# 468323_001_LED_DRV_ISO_1.net
KiCad netlist of a schematic drawn in Altium Designer
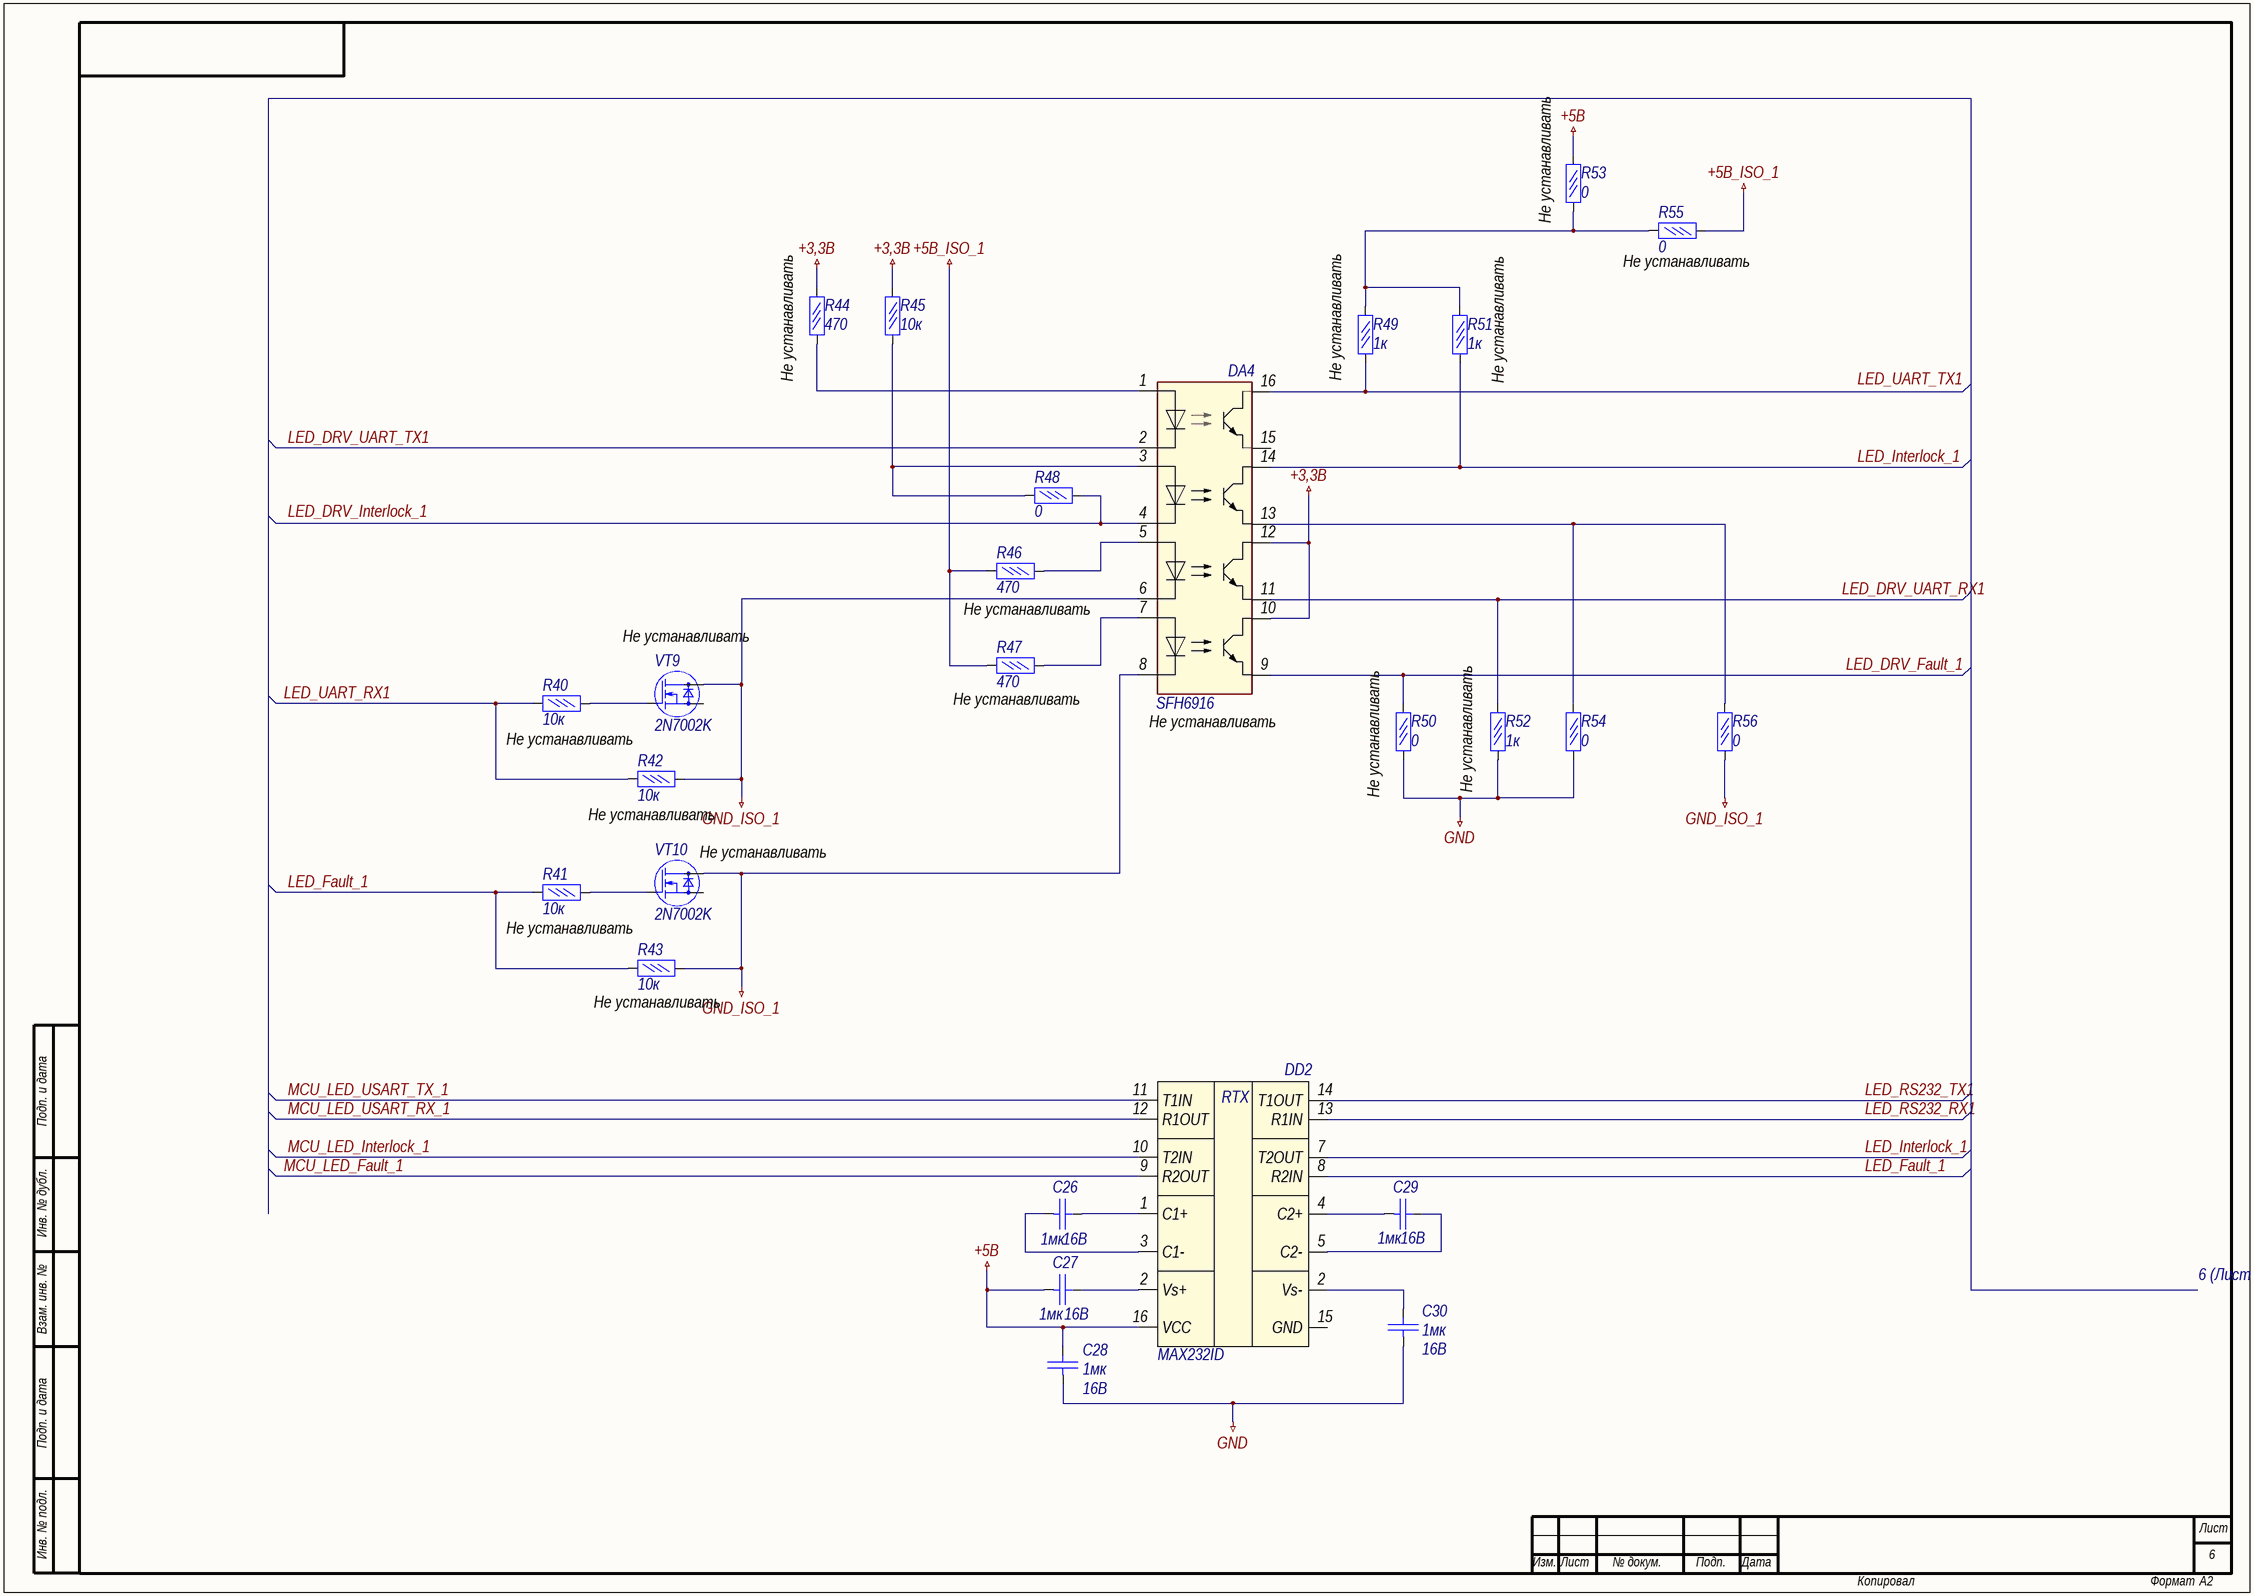
[diagram p0: РЕУН.468323.001_LED_DRV_ISO_1.SchDoc]

(export (version "E")
  (design (tool "Eeschema 10.0.6"))
  (components
    (comp (ref "C26")
      (value "1мк")
      (footprint "C0805_AA")
      (description "Конденсатор кер.")
      (fields (field (name "VOLTAGE") "16В"))
      (libsource (lib "Library_Diana") (part "Конденсатор кер."))
    )
    (comp (ref "C27")
      (value "1мк")
      (footprint "C0805_AA")
      (description "Конденсатор кер.")
      (fields (field (name "VOLTAGE") "16В"))
      (libsource (lib "Library_Diana") (part "Конденсатор кер."))
    )
    (comp (ref "C28")
      (value "1мк")
      (footprint "C0805_AA")
      (description "Конденсатор кер.")
      (fields (field (name "VOLTAGE") "16В"))
      (libsource (lib "Library_Diana") (part "Конденсатор кер."))
    )
    (comp (ref "C29")
      (value "1мк")
      (footprint "C0805_AA")
      (description "Конденсатор кер.")
      (fields (field (name "VOLTAGE") "16В"))
      (libsource (lib "Library_Diana") (part "Конденсатор кер."))
    )
    (comp (ref "C30")
      (value "1мк")
      (footprint "C0805_AA")
      (description "Конденсатор кер.")
      (fields (field (name "VOLTAGE") "16В"))
      (libsource (lib "Library_Diana") (part "Конденсатор кер."))
    )
    (comp (ref "DA4")
      (value "SFH6916")
      (description "Опторазвязка х4")
      (libsource (lib "Library_Diana") (part "OPTO-4"))
    )
    (comp (ref "DD2")
      (value "MAX232ID")
      (description "Dual EIA-232 Drivers/Receivers")
      (libsource (lib "Library_Diana") (part "MAX232ID"))
    )
    (comp (ref "R40")
      (value "10к")
      (footprint "R1206")
      (description "Резистор 0,05Вт")
      (libsource (lib "") (part "Резистор  0,05Вт_1"))
    )
    (comp (ref "R41")
      (value "10к")
      (footprint "R1206")
      (description "Резистор 0,05Вт")
      (libsource (lib "") (part "Резистор  0,05Вт_1"))
    )
    (comp (ref "R42")
      (value "10к")
      (footprint "R1206")
      (description "Резистор 0,05Вт")
      (libsource (lib "") (part "Резистор  0,05Вт_1"))
    )
    (comp (ref "R43")
      (value "10к")
      (footprint "R1206")
      (description "Резистор 0,05Вт")
      (libsource (lib "") (part "Резистор  0,05Вт_1"))
    )
    (comp (ref "R44")
      (value "470")
      (footprint "R1206")
      (description "Резистор 0,05Вт")
      (libsource (lib "") (part "Резистор  0,05Вт_2"))
    )
    (comp (ref "R45")
      (value "10к")
      (footprint "R1206")
      (description "Резистор 0,05Вт")
      (libsource (lib "Library_Diana") (part "Резистор  0,05Вт"))
    )
    (comp (ref "R46")
      (value "470")
      (footprint "R1206")
      (description "Резистор 0,05Вт")
      (libsource (lib "") (part "Резистор  0,05Вт_1"))
    )
    (comp (ref "R47")
      (value "470")
      (footprint "R1206")
      (description "Резистор 0,05Вт")
      (libsource (lib "") (part "Резистор  0,05Вт_1"))
    )
    (comp (ref "R48")
      (value "0")
      (footprint "R1206")
      (description "Резистор 0,05Вт")
      (libsource (lib "") (part "Резистор  0,05Вт_1"))
    )
    (comp (ref "R49")
      (value "1к")
      (footprint "R1206")
      (description "Резистор 0,05Вт")
      (libsource (lib "Library_Diana") (part "Резистор  0,05Вт"))
    )
    (comp (ref "R50")
      (value "0")
      (footprint "R1206")
      (description "Резистор 0,05Вт")
      (libsource (lib "Library_Diana") (part "Резистор  0,05Вт"))
    )
    (comp (ref "R51")
      (value "1к")
      (footprint "R1206")
      (description "Резистор 0,05Вт")
      (libsource (lib "Library_Diana") (part "Резистор  0,05Вт"))
    )
    (comp (ref "R52")
      (value "1к")
      (footprint "R1206")
      (description "Резистор 0,05Вт")
      (libsource (lib "Library_Diana") (part "Резистор  0,05Вт"))
    )
    (comp (ref "R53")
      (value "0")
      (footprint "R1206")
      (description "Резистор 0,05Вт")
      (libsource (lib "") (part "Резистор  0,05Вт_2"))
    )
    (comp (ref "R54")
      (value "0")
      (footprint "R1206")
      (description "Резистор 0,05Вт")
      (libsource (lib "Library_Diana") (part "Резистор  0,05Вт"))
    )
    (comp (ref "R55")
      (value "0")
      (footprint "R1206")
      (description "Резистор 0,05Вт")
      (libsource (lib "") (part "Резистор  0,05Вт_3"))
    )
    (comp (ref "R56")
      (value "0")
      (footprint "R1206")
      (description "Резистор 0,05Вт")
      (libsource (lib "Library_Diana") (part "Резистор  0,05Вт"))
    )
    (comp (ref "VT9")
      (value "2N7002K")
      (footprint "SOT:SOT23-3")
      (fields (field (name "NAME") "2N7002K"))
      (libsource (lib "Library_Diana") (part "mosfet-n"))
    )
    (comp (ref "VT10")
      (value "2N7002K")
      (footprint "SOT:SOT23-3")
      (fields (field (name "NAME") "2N7002K"))
      (libsource (lib "Library_Diana") (part "mosfet-n"))
    )
  )
  (nets
    (net (code "1") (name "+3,3В") (class "Default")
      (node (ref "DA4") (pin "10") (pintype "passive"))
      (node (ref "DA4") (pin "12") (pintype "passive"))
      (node (ref "R44") (pin "1") (pinfunction "1_1") (pintype "passive"))
      (node (ref "R45") (pin "2") (pinfunction "2_2") (pintype "passive"))
    )
    (net (code "2") (name "+5В") (class "Default")
      (node (ref "C27") (pin "2") (pinfunction "2_2") (pintype "passive"))
      (node (ref "C28") (pin "1") (pinfunction "1_1") (pintype "passive"))
      (node (ref "DD2") (pin "16") (pinfunction "VCC_16") (pintype "passive"))
      (node (ref "R53") (pin "1") (pinfunction "1_1") (pintype "passive"))
    )
    (net (code "3") (name "+5В_ISO_1") (class "Default")
      (node (ref "R46") (pin "1") (pinfunction "1_1") (pintype "passive"))
      (node (ref "R47") (pin "1") (pinfunction "1_1") (pintype "passive"))
      (node (ref "R55") (pin "1") (pinfunction "1_1") (pintype "passive"))
    )
    (net (code "4") (name "/LED_DRV_Fault_1") (class "Default")
      (node (ref "DA4") (pin "9") (pintype "passive"))
      (node (ref "R50") (pin "2") (pinfunction "2_2") (pintype "passive"))
    )
    (net (code "6") (name "/LED_DRV_UART_RX1") (class "Default")
      (node (ref "DA4") (pin "11") (pintype "passive"))
      (node (ref "R52") (pin "2") (pinfunction "2_2") (pintype "passive"))
    )
    (net (code "7") (name "/LED_DRV_UART_TX1") (class "Default")
      (node (ref "DA4") (pin "2") (pintype "passive"))
    )
    (net (code "8") (name "/LED_Fault_1") (class "Default")
      (node (ref "DD2") (pin "8") (pinfunction "R2IN_8") (pintype "passive"))
      (node (ref "R41") (pin "1") (pinfunction "1_1") (pintype "passive"))
      (node (ref "R43") (pin "1") (pinfunction "1_1") (pintype "passive"))
    )
    (net (code "9") (name "/LED_Interlock_1") (class "Default")
      (node (ref "DA4") (pin "14") (pintype "passive"))
      (node (ref "DD2") (pin "7") (pinfunction "T2OUT_7") (pintype "passive"))
      (node (ref "R51") (pin "1") (pinfunction "1_1") (pintype "passive"))
    )
    (net (code "10") (name "/LED_RS232_RX1") (class "Default")
      (node (ref "DD2") (pin "13") (pinfunction "R1IN_13") (pintype "passive"))
    )
    (net (code "11") (name "/LED_RS232_TX1") (class "Default")
      (node (ref "DD2") (pin "14") (pinfunction "T1OUT_14") (pintype "passive"))
    )
    (net (code "12") (name "/LED_UART_RX1") (class "Default")
      (node (ref "R40") (pin "1") (pinfunction "1_1") (pintype "passive"))
      (node (ref "R42") (pin "1") (pinfunction "1_1") (pintype "passive"))
    )
    (net (code "14") (name "/MCU_LED_Fault_1") (class "Default")
      (node (ref "DD2") (pin "9") (pinfunction "R2OUT_9") (pintype "passive"))
    )
    (net (code "15") (name "/MCU_LED_Interlock_1") (class "Default")
      (node (ref "DD2") (pin "10") (pinfunction "T2IN_10") (pintype "passive"))
    )
    (net (code "16") (name "/MCU_LED_USART_RX_1") (class "Default")
      (node (ref "DD2") (pin "12") (pinfunction "R1OUT_12") (pintype "passive"))
    )
    (net (code "17") (name "/MCU_LED_USART_TX_1") (class "Default")
      (node (ref "DD2") (pin "11") (pinfunction "T1IN_11") (pintype "passive"))
    )
    (net (code "18") (name "GND") (class "Default")
      (node (ref "C28") (pin "2") (pinfunction "2_2") (pintype "passive"))
      (node (ref "C30") (pin "2") (pinfunction "2_2") (pintype "passive"))
      (node (ref "R50") (pin "1") (pinfunction "1_1") (pintype "passive"))
      (node (ref "R52") (pin "1") (pinfunction "1_1") (pintype "passive"))
      (node (ref "R54") (pin "1") (pinfunction "1_1") (pintype "passive"))
    )
    (net (code "19") (name "GND_ISO_1") (class "Default")
      (node (ref "DA4") (pin "6") (pintype "passive"))
      (node (ref "DA4") (pin "8") (pintype "passive"))
      (node (ref "R42") (pin "2") (pinfunction "2_2") (pintype "passive"))
      (node (ref "R43") (pin "2") (pinfunction "2_2") (pintype "passive"))
      (node (ref "R56") (pin "1") (pinfunction "1_1") (pintype "passive"))
      (node (ref "VT10") (pin "3") (pinfunction "D_3") (pintype "passive"))
      (node (ref "VT9") (pin "3") (pinfunction "D_3") (pintype "passive"))
    )
    (net (code "20") (name "Net-(DA4-Pad1)") (class "Default")
      (node (ref "DA4") (pin "1") (pintype "passive"))
      (node (ref "R44") (pin "2") (pinfunction "2_2") (pintype "passive"))
    )
    (net (code "21") (name "Net-(DA4-Pad3)") (class "Default")
      (node (ref "DA4") (pin "3") (pintype "passive"))
      (node (ref "R45") (pin "1") (pinfunction "1_1") (pintype "passive"))
      (node (ref "R48") (pin "1") (pinfunction "1_1") (pintype "passive"))
    )
    (net (code "22") (name "Net-(DA4-Pad4)") (class "Default")
      (node (ref "DA4") (pin "4") (pintype "passive"))
      (node (ref "R48") (pin "2") (pinfunction "2_2") (pintype "passive"))
    )
    (net (code "23") (name "Net-(DA4-Pad5)") (class "Default")
      (node (ref "DA4") (pin "5") (pintype "passive"))
      (node (ref "R46") (pin "2") (pinfunction "2_2") (pintype "passive"))
    )
    (net (code "24") (name "Net-(DA4-Pad7)") (class "Default")
      (node (ref "DA4") (pin "7") (pintype "passive"))
      (node (ref "R47") (pin "2") (pinfunction "2_2") (pintype "passive"))
    )
    (net (code "25") (name "Net-(DA4-Pad13)") (class "Default")
      (node (ref "DA4") (pin "13") (pintype "passive"))
      (node (ref "R54") (pin "2") (pinfunction "2_2") (pintype "passive"))
      (node (ref "R56") (pin "2") (pinfunction "2_2") (pintype "passive"))
    )
    (net (code "26") (name "Net-(DA4-Pad16)") (class "Default")
      (node (ref "DA4") (pin "16") (pintype "passive"))
      (node (ref "R49") (pin "1") (pinfunction "1_1") (pintype "passive"))
    )
    (net (code "27") (name "Net-(DD2-C1+)") (class "Default")
      (node (ref "C26") (pin "1") (pinfunction "1_1") (pintype "passive"))
      (node (ref "DD2") (pin "1") (pinfunction "C1+_1") (pintype "passive"))
    )
    (net (code "28") (name "Net-(DD2-C1-)") (class "Default")
      (node (ref "C26") (pin "2") (pinfunction "2_2") (pintype "passive"))
      (node (ref "DD2") (pin "3") (pinfunction "C1-_3") (pintype "passive"))
    )
    (net (code "29") (name "Net-(DD2-C2+)") (class "Default")
      (node (ref "C29") (pin "2") (pinfunction "2_2") (pintype "passive"))
      (node (ref "DD2") (pin "4") (pinfunction "C2+_4") (pintype "passive"))
    )
    (net (code "30") (name "Net-(DD2-C2-)") (class "Default")
      (node (ref "C29") (pin "1") (pinfunction "1_1") (pintype "passive"))
      (node (ref "DD2") (pin "5") (pinfunction "C2-_5") (pintype "passive"))
    )
    (net (code "31") (name "Net-(DD2-Vs+)") (class "Default")
      (node (ref "C27") (pin "1") (pinfunction "1_1") (pintype "passive"))
      (node (ref "DD2") (pin "2") (pinfunction "Vs+_2") (pintype "passive"))
    )
    (net (code "32") (name "Net-(DD2-Vs-)") (class "Default")
      (node (ref "C30") (pin "1") (pinfunction "1_1") (pintype "passive"))
      (node (ref "DD2") (pin "2") (pinfunction "Vs-_2") (pintype "passive"))
    )
    (net (code "33") (name "Net-(R49-Pad2)") (class "Default")
      (node (ref "R49") (pin "2") (pinfunction "2_2") (pintype "passive"))
      (node (ref "R51") (pin "2") (pinfunction "2_2") (pintype "passive"))
      (node (ref "R53") (pin "2") (pinfunction "2_2") (pintype "passive"))
      (node (ref "R55") (pin "2") (pinfunction "2_2") (pintype "passive"))
    )
    (net (code "34") (name "Net-(VT9-G)") (class "Default")
      (node (ref "R40") (pin "2") (pinfunction "2_2") (pintype "passive"))
      (node (ref "VT9") (pin "1") (pinfunction "G_1") (pintype "passive"))
    )
    (net (code "35") (name "Net-(VT10-G)") (class "Default")
      (node (ref "R41") (pin "2") (pinfunction "2_2") (pintype "passive"))
      (node (ref "VT10") (pin "1") (pinfunction "G_1") (pintype "passive"))
    )
    (net (code "36") (name "unconnected-(DA4-Pad15)") (class "Default")
      (node (ref "DA4") (pin "15") (pintype "passive"))
    )
    (net (code "37") (name "unconnected-(DD2-GND-Pad15)") (class "Default")
      (node (ref "DD2") (pin "15") (pinfunction "GND_15") (pintype "passive"))
    )
    (net (code "38") (name "unconnected-(VT9-S-Pad2)") (class "Default")
      (node (ref "VT9") (pin "2") (pinfunction "S_2") (pintype "passive"))
    )
    (net (code "39") (name "unconnected-(VT10-S-Pad2)") (class "Default")
      (node (ref "VT10") (pin "2") (pinfunction "S_2") (pintype "passive"))
    )
  )
)
